# tu_lam_bai_1.net
KiCad netlist of a schematic drawn in Altium Designer
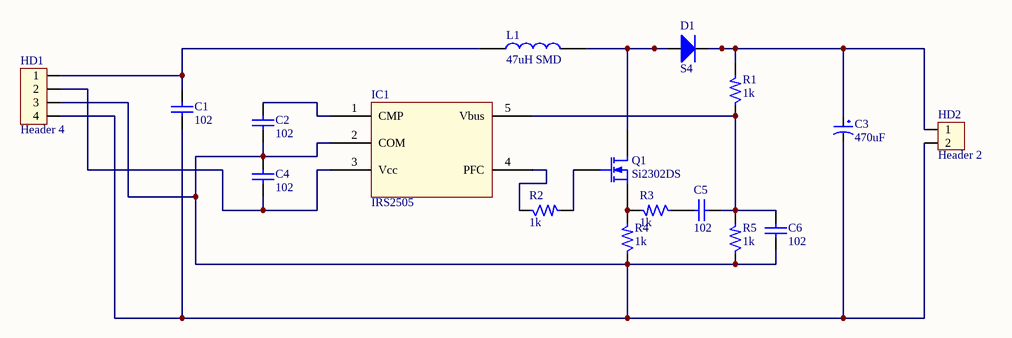
[diagram p0: tu lam bai 1.SchDoc]

(export (version "E")
  (design (tool "Eeschema 10.0.6"))
  (components
    (comp (ref "C1")
      (value "102")
      (footprint "tu 0603")
      (description "Dán")
      (libsource (lib "Tu dien") (part "Tu 0603 102 50V 10%"))
    )
    (comp (ref "C2")
      (value "102")
      (footprint "tu 0603")
      (description "Dán")
      (libsource (lib "Tu dien") (part "Tu 0603 102 50V 10%"))
    )
    (comp (ref "C3")
      (value "470uF")
      (footprint "tu tantalum smd7343")
      (description "Dán")
      (libsource (lib "Tu dien") (part "Tu tantalum 470uF 10V SMD7343"))
    )
    (comp (ref "C4")
      (value "102")
      (footprint "tu 0603")
      (description "Dán")
      (libsource (lib "Tu dien") (part "Tu 0603 102 50V 10%"))
    )
    (comp (ref "C5")
      (value "102")
      (footprint "tu 0603")
      (description "Dán")
      (libsource (lib "Tu dien") (part "Tu 0603 102 50V 10%"))
    )
    (comp (ref "C6")
      (value "102")
      (footprint "tu 0603")
      (description "Dán")
      (libsource (lib "Tu dien") (part "Tu 0603 102 50V 10%"))
    )
    (comp (ref "D1")
      (value "S4")
      (footprint "DIODE SOD-123")
      (description "Dán")
      (libsource (lib "Diode") (part "Diode S4"))
    )
    (comp (ref "HD1")
      (value "Header 4")
      (footprint "HED4")
      (description "Header 4 (Green)")
      (libsource (lib "syhaunguyen") (part "Hed4"))
    )
    (comp (ref "HD2")
      (value "Header 2")
      (footprint "HED2")
      (description "Header 2 (Green)")
      (libsource (lib "syhaunguyen") (part "Hed2"))
    )
    (comp (ref "IC1") (value "IRS2505") (footprint "IRS2505") (libsource (lib "TV NQM") (part "IRS2505")))
    (comp (ref "L1")
      (value "47uH SMD")
      (footprint "Cuon Cam 7x7x5")
      (description "Dán")
      (libsource (lib "Cuon Cam") (part "CUON CAM 47uH SMD"))
    )
    (comp (ref "Q1")
      (value "Si2302DS")
      (footprint "SOT23")
      (description "N-Channel MOSFET")
      (fields (field (name "PUBLISHER") "Altium Limited"))
      (libsource (lib "syhaunguyen") (part "Si2302DS"))
    )
    (comp (ref "R1")
      (value "1k")
      (footprint "SM-RES-1206")
      (description "Resistor 1/4W")
      (libsource (lib "syhaunguyen") (part "R"))
    )
    (comp (ref "R2")
      (value "1k")
      (footprint "SM-RES-1206")
      (description "Resistor 1/4W")
      (libsource (lib "syhaunguyen") (part "R"))
    )
    (comp (ref "R3")
      (value "1k")
      (footprint "SM-RES-1206")
      (description "Resistor 1/4W")
      (libsource (lib "syhaunguyen") (part "R"))
    )
    (comp (ref "R4")
      (value "1k")
      (footprint "SM-RES-1206")
      (description "Resistor 1/4W")
      (libsource (lib "syhaunguyen") (part "R"))
    )
    (comp (ref "R5")
      (value "1k")
      (footprint "SM-RES-1206")
      (description "Resistor 1/4W")
      (libsource (lib "syhaunguyen") (part "R"))
    )
  )
  (nets
    (net (code "1") (name "Net-(C1-Pad1)") (class "Default")
      (node (ref "C1") (pin "1") (pinfunction "1_1") (pintype "passive"))
      (node (ref "HD1") (pin "1") (pinfunction "1_1") (pintype "passive"))
      (node (ref "L1") (pin "1") (pinfunction "1_1") (pintype "passive"))
    )
    (net (code "2") (name "Net-(C5-Pad1)") (class "Default")
      (node (ref "C5") (pin "1") (pinfunction "1_1") (pintype "passive"))
      (node (ref "R3") (pin "1") (pinfunction "1_1") (pintype "passive"))
    )
    (net (code "3") (name "Net-(D1-A)") (class "Default")
      (node (ref "D1") (pin "1") (pinfunction "A_1") (pintype "passive"))
      (node (ref "L1") (pin "2") (pinfunction "2_2") (pintype "passive"))
      (node (ref "Q1") (pin "3") (pinfunction "D_3") (pintype "passive"))
    )
    (net (code "4") (name "Net-(D1-K)") (class "Default")
      (node (ref "C3") (pin "1") (pinfunction "1_1") (pintype "passive"))
      (node (ref "D1") (pin "2") (pinfunction "K_2") (pintype "passive"))
      (node (ref "HD2") (pin "1") (pinfunction "1_1") (pintype "passive"))
      (node (ref "R1") (pin "2") (pinfunction "2_2") (pintype "passive"))
    )
    (net (code "5") (name "Net-(IC1-CMP)") (class "Default")
      (node (ref "C2") (pin "1") (pinfunction "1_1") (pintype "passive"))
      (node (ref "IC1") (pin "1") (pinfunction "CMP_1") (pintype "passive"))
    )
    (net (code "6") (name "Net-(IC1-COM)") (class "Default")
      (node (ref "C1") (pin "2") (pinfunction "2_2") (pintype "passive"))
      (node (ref "C2") (pin "2") (pinfunction "2_2") (pintype "passive"))
      (node (ref "C3") (pin "2") (pinfunction "2_2") (pintype "passive"))
      (node (ref "C4") (pin "1") (pinfunction "1_1") (pintype "passive"))
      (node (ref "C6") (pin "1") (pinfunction "1_1") (pintype "passive"))
      (node (ref "HD1") (pin "3") (pinfunction "3_3") (pintype "passive"))
      (node (ref "HD1") (pin "4") (pinfunction "4_4") (pintype "passive"))
      (node (ref "HD2") (pin "2") (pinfunction "2_2") (pintype "passive"))
      (node (ref "IC1") (pin "2") (pinfunction "COM_2") (pintype "passive"))
      (node (ref "R4") (pin "1") (pinfunction "1_1") (pintype "passive"))
      (node (ref "R5") (pin "1") (pinfunction "1_1") (pintype "passive"))
    )
    (net (code "7") (name "Net-(IC1-PFC)") (class "Default")
      (node (ref "IC1") (pin "4") (pinfunction "PFC_4") (pintype "passive"))
      (node (ref "R2") (pin "1") (pinfunction "1_1") (pintype "passive"))
    )
    (net (code "8") (name "Net-(IC1-Vbus)") (class "Default")
      (node (ref "C5") (pin "2") (pinfunction "2_2") (pintype "passive"))
      (node (ref "C6") (pin "2") (pinfunction "2_2") (pintype "passive"))
      (node (ref "IC1") (pin "5") (pinfunction "Vbus_5") (pintype "passive"))
      (node (ref "R1") (pin "1") (pinfunction "1_1") (pintype "passive"))
      (node (ref "R5") (pin "2") (pinfunction "2_2") (pintype "passive"))
    )
    (net (code "9") (name "Net-(IC1-Vcc)") (class "Default")
      (node (ref "C4") (pin "2") (pinfunction "2_2") (pintype "passive"))
      (node (ref "HD1") (pin "2") (pinfunction "2_2") (pintype "passive"))
      (node (ref "IC1") (pin "3") (pinfunction "Vcc_3") (pintype "passive"))
    )
    (net (code "10") (name "Net-(Q1-G)") (class "Default")
      (node (ref "Q1") (pin "1") (pinfunction "G_1") (pintype "passive"))
      (node (ref "R2") (pin "2") (pinfunction "2_2") (pintype "passive"))
    )
    (net (code "11") (name "Net-(Q1-S)") (class "Default")
      (node (ref "Q1") (pin "2") (pinfunction "S_2") (pintype "passive"))
      (node (ref "R3") (pin "2") (pinfunction "2_2") (pintype "passive"))
      (node (ref "R4") (pin "2") (pinfunction "2_2") (pintype "passive"))
    )
  )
)
